# midicontroller.net
KiCad netlist of a schematic drawn in EAGLE
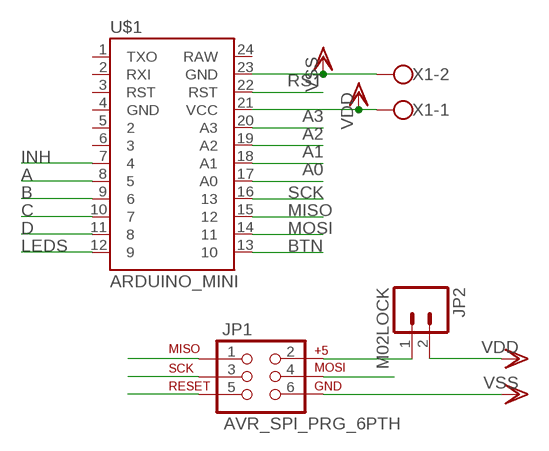
[diagram p0: schematic, sheet 1]

(export (version "E")
  (design (tool "Eeschema 10.0.6"))
  (components
    (comp (ref "JP1")
      (value "AVR_SPI_PRG_6PTH")
      (footprint "eagle-import:2X3")
      (libsource (lib "eagle-import") (part "AVR_SPI_PRG_6PTH"))
    )
    (comp (ref "JP2")
      (value "M02LOCK")
      (footprint "eagle-import:1X02_LOCK")
      (libsource (lib "eagle-import") (part "M02LOCK"))
    )
    (comp (ref "U$1")
      (value "ARDUINO_MINI")
      (footprint "eagle-import:ARDUINO_MINI")
      (libsource (lib "eagle-import") (part "ARDUINO_MINI"))
    )
    (comp (ref "X1")
      (value "W237-102")
      (footprint "eagle-import:W237-102")
      (fields (field (name "MPN") "237-102"))
      (libsource (lib "eagle-import") (part "W237-102"))
    )
  )
  (nets
    (net (code "1") (name "/A") (class "Default")
      (node (ref "U$1") (pin "8") (pinfunction "5_8") (pintype "bidirectional"))
    )
    (net (code "2") (name "/A0") (class "Default")
      (node (ref "U$1") (pin "17") (pinfunction "A0_17") (pintype "bidirectional"))
    )
    (net (code "3") (name "/A1") (class "Default")
      (node (ref "U$1") (pin "18") (pinfunction "A1_18") (pintype "bidirectional"))
    )
    (net (code "4") (name "/A2") (class "Default")
      (node (ref "U$1") (pin "19") (pinfunction "A2_19") (pintype "bidirectional"))
    )
    (net (code "5") (name "/A3") (class "Default")
      (node (ref "U$1") (pin "20") (pinfunction "A3_20") (pintype "bidirectional"))
    )
    (net (code "6") (name "/B") (class "Default")
      (node (ref "U$1") (pin "9") (pinfunction "6_9") (pintype "bidirectional"))
    )
    (net (code "7") (name "/BTN") (class "Default")
      (node (ref "U$1") (pin "13") (pinfunction "10_13") (pintype "bidirectional"))
    )
    (net (code "8") (name "/C") (class "Default")
      (node (ref "U$1") (pin "10") (pinfunction "7_10") (pintype "bidirectional"))
    )
    (net (code "9") (name "/D") (class "Default")
      (node (ref "U$1") (pin "11") (pinfunction "8_11") (pintype "bidirectional"))
    )
    (net (code "10") (name "/INH") (class "Default")
      (node (ref "U$1") (pin "7") (pinfunction "4_7") (pintype "bidirectional"))
    )
    (net (code "11") (name "/LEDS") (class "Default")
      (node (ref "U$1") (pin "12") (pinfunction "9_12") (pintype "bidirectional"))
    )
    (net (code "12") (name "/MISO") (class "Default")
      (node (ref "JP1") (pin "1") (pinfunction "1_1") (pintype "passive"))
      (node (ref "U$1") (pin "15") (pinfunction "12_15") (pintype "bidirectional"))
    )
    (net (code "13") (name "/MOSI") (class "Default")
      (node (ref "JP1") (pin "4") (pinfunction "4_4") (pintype "passive"))
      (node (ref "U$1") (pin "14") (pinfunction "11_14") (pintype "bidirectional"))
    )
    (net (code "14") (name "/RST") (class "Default")
      (node (ref "JP1") (pin "5") (pinfunction "5_5") (pintype "passive"))
      (node (ref "U$1") (pin "22") (pinfunction "RST_22") (pintype "bidirectional"))
    )
    (net (code "15") (name "/SCK") (class "Default")
      (node (ref "JP1") (pin "3") (pinfunction "3_3") (pintype "passive"))
      (node (ref "U$1") (pin "16") (pinfunction "13_16") (pintype "bidirectional"))
    )
    (net (code "16") (name "Net-(JP1-Pad2)") (class "Default")
      (node (ref "JP1") (pin "2") (pinfunction "2_2") (pintype "passive"))
      (node (ref "JP2") (pin "1") (pinfunction "1_1") (pintype "passive"))
    )
    (net (code "17") (name "VDD") (class "Default")
      (node (ref "JP2") (pin "2") (pinfunction "2_2") (pintype "passive"))
      (node (ref "U$1") (pin "21") (pinfunction "VCC_21") (pintype "bidirectional"))
      (node (ref "X1") (pin "1") (pinfunction "KL_1") (pintype "passive"))
    )
    (net (code "18") (name "VSS") (class "Default")
      (node (ref "JP1") (pin "6") (pinfunction "6_6") (pintype "passive"))
      (node (ref "U$1") (pin "23") (pinfunction "GND_23") (pintype "bidirectional"))
      (node (ref "X1") (pin "2") (pinfunction "KL_2") (pintype "passive"))
    )
    (net (code "19") (name "unconnected-(U$1-2-Pad5)") (class "Default")
      (node (ref "U$1") (pin "5") (pinfunction "2_5") (pintype "bidirectional"))
    )
    (net (code "20") (name "unconnected-(U$1-3-Pad6)") (class "Default")
      (node (ref "U$1") (pin "6") (pinfunction "3_6") (pintype "bidirectional"))
    )
    (net (code "21") (name "unconnected-(U$1-GND-Pad4)") (class "Default")
      (node (ref "U$1") (pin "4") (pinfunction "GND_4") (pintype "bidirectional"))
    )
    (net (code "22") (name "unconnected-(U$1-RAW-Pad24)") (class "Default")
      (node (ref "U$1") (pin "24") (pinfunction "RAW_24") (pintype "bidirectional"))
    )
    (net (code "23") (name "unconnected-(U$1-RST-Pad3)") (class "Default")
      (node (ref "U$1") (pin "3") (pinfunction "RST_3") (pintype "bidirectional"))
    )
    (net (code "24") (name "unconnected-(U$1-RXI-Pad2)") (class "Default")
      (node (ref "U$1") (pin "2") (pinfunction "RXI_2") (pintype "bidirectional"))
    )
    (net (code "25") (name "unconnected-(U$1-TXO-Pad1)") (class "Default")
      (node (ref "U$1") (pin "1") (pinfunction "TXO_1") (pintype "bidirectional"))
    )
  )
)
